# untitled.net
KiCad netlist of a schematic drawn in EAGLE
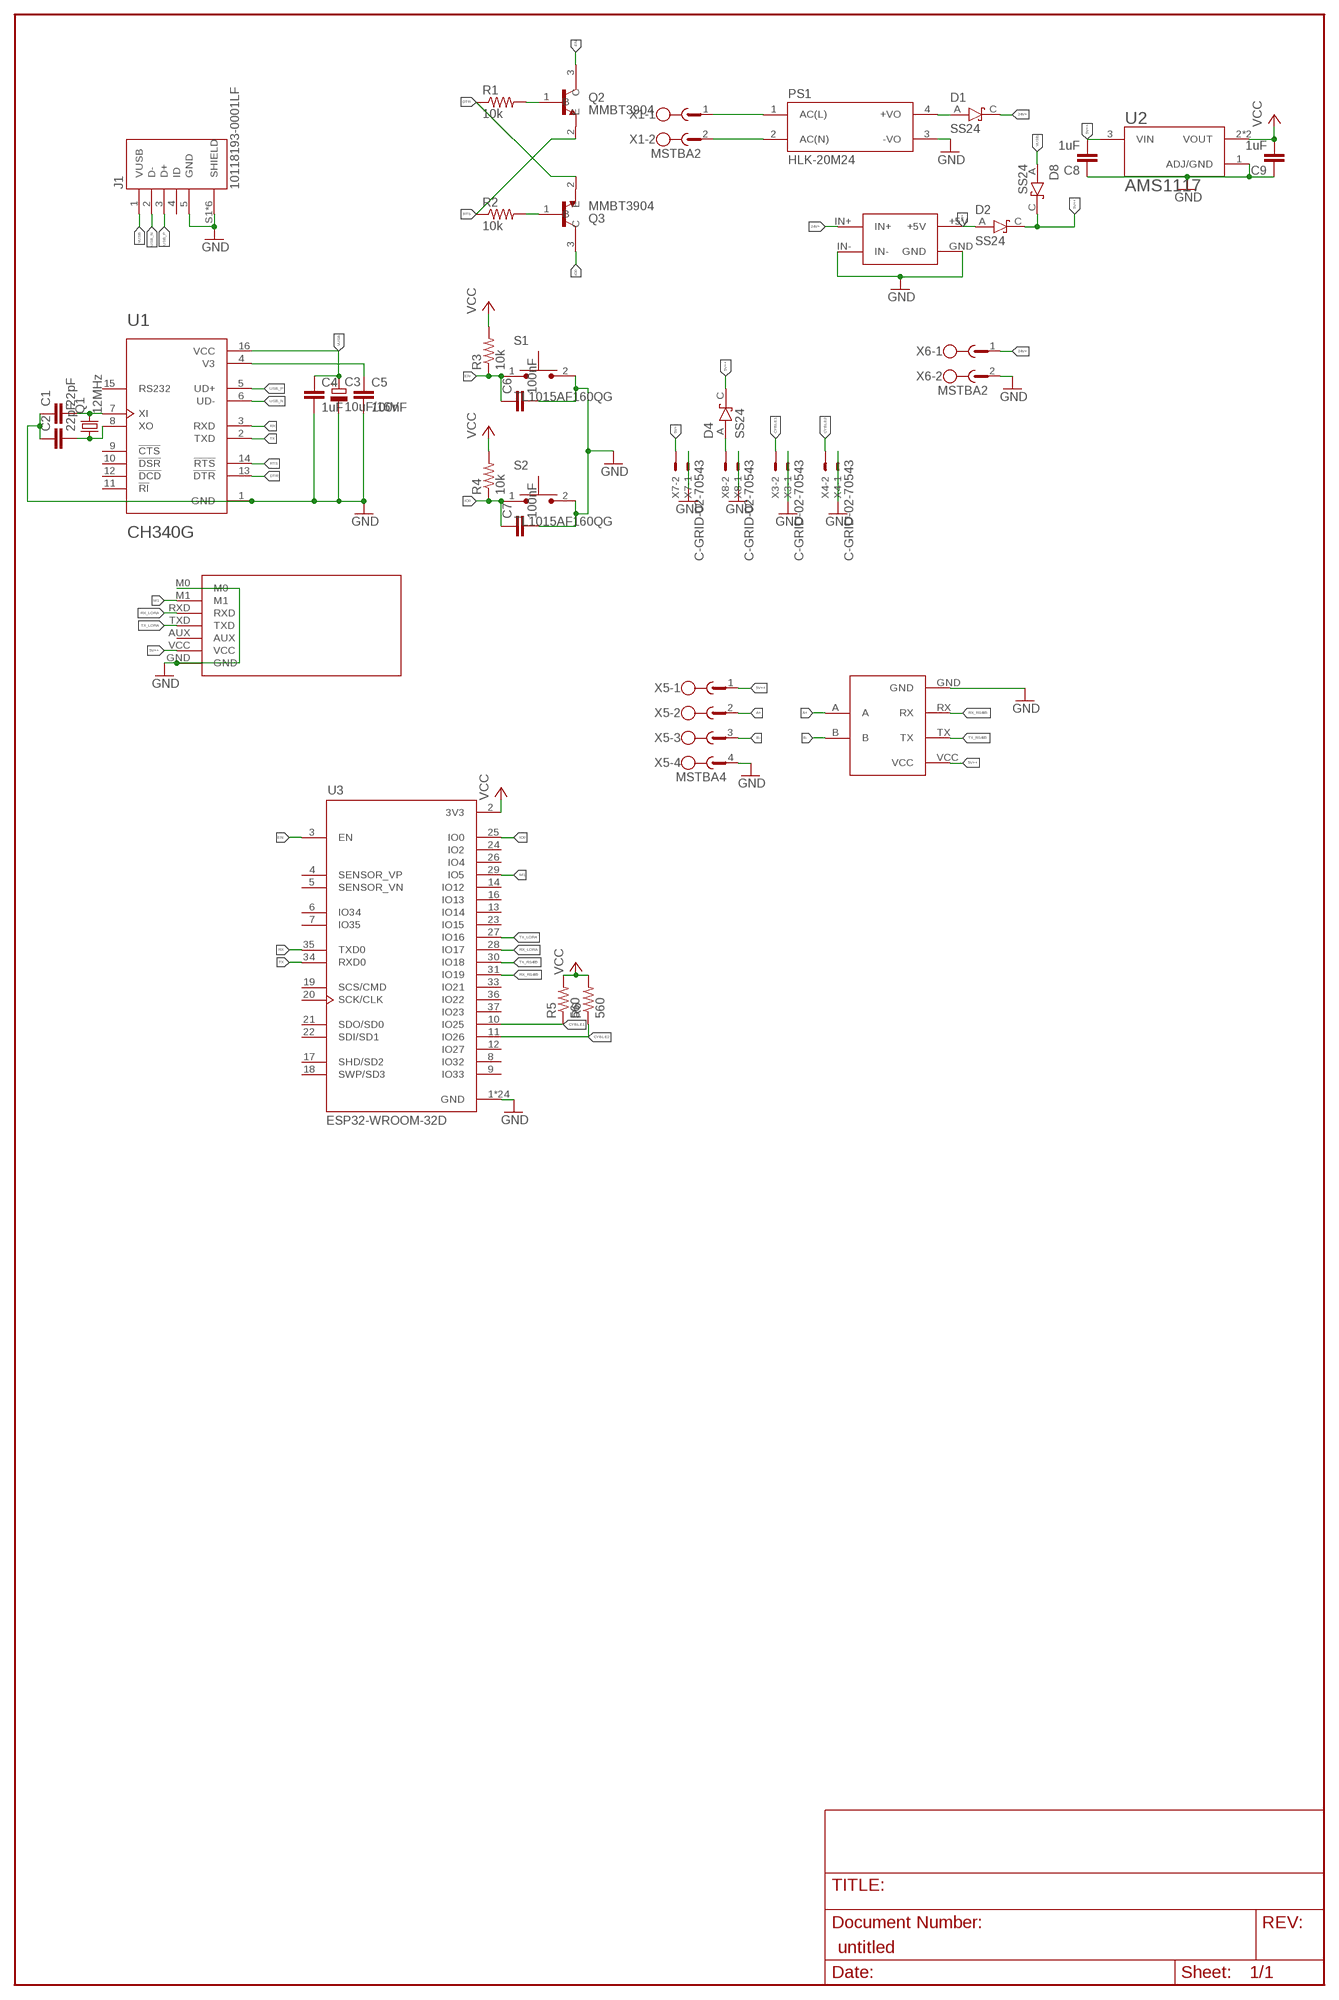
[diagram p0: schematic, sheet 1]

(export (version "E")
  (design (tool "Eeschema 10.0.6"))
  (components
    (comp (ref "C1")
      (value "22pF")
      (footprint "eagle-import:C0805K")
      (libsource (lib "eagle-import") (part "C-EUC0805K"))
    )
    (comp (ref "C2")
      (value "22pF")
      (footprint "eagle-import:C0805K")
      (libsource (lib "eagle-import") (part "C-EUC0805K"))
    )
    (comp (ref "C3")
      (value "10uF/16V")
      (footprint "eagle-import:153CLV-0505")
      (libsource (lib "eagle-import") (part "CPOL-EU153CLV-0505"))
    )
    (comp (ref "C4")
      (value "1uF")
      (footprint "eagle-import:C0805K")
      (libsource (lib "eagle-import") (part "C-EUC0805K"))
    )
    (comp (ref "C5")
      (value "100nF")
      (footprint "eagle-import:C0805K")
      (libsource (lib "eagle-import") (part "C-EUC0805K"))
    )
    (comp (ref "C6")
      (value "100nF")
      (footprint "eagle-import:C0805K")
      (libsource (lib "eagle-import") (part "C-EUC0805K"))
    )
    (comp (ref "C7")
      (value "100nF")
      (footprint "eagle-import:C0805K")
      (libsource (lib "eagle-import") (part "C-EUC0805K"))
    )
    (comp (ref "C8")
      (value "1uF")
      (footprint "eagle-import:C0805K")
      (libsource (lib "eagle-import") (part "C-EUC0805K"))
    )
    (comp (ref "C9")
      (value "1uF")
      (footprint "eagle-import:C0805K")
      (libsource (lib "eagle-import") (part "C-EUC0805K"))
    )
    (comp (ref "D1")
      (value "SS24")
      (footprint "eagle-import:DIOM5336X265N")
      (fields (field (name "MF") "ON Semiconductor"))
      (libsource (lib "eagle-import") (part "SS24"))
    )
    (comp (ref "D2")
      (value "SS24")
      (footprint "eagle-import:DIOM5336X265N")
      (fields (field (name "MF") "ON Semiconductor"))
      (libsource (lib "eagle-import") (part "SS24"))
    )
    (comp (ref "D4")
      (value "SS24")
      (footprint "eagle-import:DIOM5336X265N")
      (fields (field (name "MF") "ON Semiconductor"))
      (libsource (lib "eagle-import") (part "SS24"))
    )
    (comp (ref "D8")
      (value "SS24")
      (footprint "eagle-import:DIOM5336X265N")
      (fields (field (name "MF") "ON Semiconductor"))
      (libsource (lib "eagle-import") (part "SS24"))
    )
    (comp (ref "EBYTEE220-900T22D1")
      (value "EBYTEE220-900T22D")
      (footprint "eagle-import:EBYTEE220-900T22D")
      (libsource (lib "eagle-import") (part "EBYTEE220-900T22D"))
    )
    (comp (ref "J1")
      (value "10118193-0001LF")
      (footprint "eagle-import:FCI_10118193-0001LF")
      (fields (field (name "MF") "FCI"))
      (libsource (lib "eagle-import") (part "10118193-0001LF"))
    )
    (comp (ref "PS1")
      (value "HLK-20M24")
      (footprint "eagle-import:CONV_HLK-20M24")
      (fields (field (name "MF") "Hi-link"))
      (libsource (lib "eagle-import") (part "HLK-20M24"))
    )
    (comp (ref "Q1")
      (value "12MHz")
      (footprint "eagle-import:SM49")
      (libsource (lib "eagle-import") (part "CRYSTALSM49"))
    )
    (comp (ref "Q2")
      (value "MMBT3904")
      (footprint "eagle-import:SOT95P240X120-3N")
      (fields (field (name "MF") "ON Semiconductor"))
      (libsource (lib "eagle-import") (part "MMBT3904"))
    )
    (comp (ref "Q3")
      (value "MMBT3904")
      (footprint "eagle-import:SOT95P240X120-3N")
      (fields (field (name "MF") "ON Semiconductor"))
      (libsource (lib "eagle-import") (part "MMBT3904"))
    )
    (comp (ref "R1")
      (value "10k")
      (footprint "eagle-import:M0805")
      (libsource (lib "eagle-import") (part "R-US_M0805"))
    )
    (comp (ref "R2")
      (value "10k")
      (footprint "eagle-import:M0805")
      (libsource (lib "eagle-import") (part "R-US_M0805"))
    )
    (comp (ref "R3")
      (value "10k")
      (footprint "eagle-import:M0805")
      (libsource (lib "eagle-import") (part "R-US_M0805"))
    )
    (comp (ref "R4")
      (value "10k")
      (footprint "eagle-import:M0805")
      (libsource (lib "eagle-import") (part "R-US_M0805"))
    )
    (comp (ref "R5")
      (value "560")
      (footprint "eagle-import:M0805")
      (libsource (lib "eagle-import") (part "R-US_M0805"))
    )
    (comp (ref "R6")
      (value "560")
      (footprint "eagle-import:M0805")
      (libsource (lib "eagle-import") (part "R-US_M0805"))
    )
    (comp (ref "S1")
      (value "TL1015AF160QG")
      (footprint "eagle-import:SW_TL1015AF160QG")
      (fields (field (name "MF") "E-Switch"))
      (libsource (lib "eagle-import") (part "TL1015AF160QG"))
    )
    (comp (ref "S2")
      (value "TL1015AF160QG")
      (footprint "eagle-import:SW_TL1015AF160QG")
      (fields (field (name "MF") "E-Switch"))
      (libsource (lib "eagle-import") (part "TL1015AF160QG"))
    )
    (comp (ref "SUPER-STEPDOWN1")
      (value "SUPER-STEPDOWN")
      (footprint "eagle-import:SUPER-STEPDOWN")
      (libsource (lib "eagle-import") (part "SUPER-STEPDOWN"))
    )
    (comp (ref "TTL-RS1")
      (value "TTL-RS485")
      (footprint "eagle-import:TTL-RS485")
      (libsource (lib "eagle-import") (part "TTL-RS485"))
    )
    (comp (ref "U1")
      (value "CH340G")
      (footprint "eagle-import:SOIC127P600X180-16N")
      (fields (field (name "MF") "WCH") (field (name "MP") "Ch340G"))
      (libsource (lib "eagle-import") (part "CH340G"))
    )
    (comp (ref "U2")
      (value "AMS1117")
      (footprint "eagle-import:SOT229P700X180-4N")
      (fields (field (name "MF") "Advanced Monolithic Systems"))
      (libsource (lib "eagle-import") (part "AMS1117"))
    )
    (comp (ref "U3")
      (value "ESP32-WROOM-32D")
      (footprint "eagle-import:MODULE_ESP32-WROOM-32D")
      (fields (field (name "MF") "Espressif Systems"))
      (libsource (lib "eagle-import") (part "ESP32-WROOM-32D"))
    )
    (comp (ref "X1")
      (value "MSTBA2")
      (footprint "eagle-import:MSTBA2")
      (fields (field (name "MF") "FARNELL") (field (name "MPN") "1757242"))
      (libsource (lib "eagle-import") (part "MSTBA2"))
    )
    (comp (ref "X3")
      (value "C-GRID-02-70543")
      (footprint "eagle-import:70543-02")
      (fields (field (name "MF") "MOLEX"))
      (libsource (lib "eagle-import") (part "C-GRID-02-70543"))
    )
    (comp (ref "X4")
      (value "C-GRID-02-70543")
      (footprint "eagle-import:70543-02")
      (fields (field (name "MF") "MOLEX"))
      (libsource (lib "eagle-import") (part "C-GRID-02-70543"))
    )
    (comp (ref "X5")
      (value "MSTBA4")
      (footprint "eagle-import:MSTBA4")
      (fields (field (name "MF") "FARNELL") (field (name "MPN") "1757268"))
      (libsource (lib "eagle-import") (part "MSTBA4"))
    )
    (comp (ref "X6")
      (value "MSTBA2")
      (footprint "eagle-import:MSTBA2")
      (fields (field (name "MF") "FARNELL") (field (name "MPN") "1757242"))
      (libsource (lib "eagle-import") (part "MSTBA2"))
    )
    (comp (ref "X7")
      (value "C-GRID-02-70543")
      (footprint "eagle-import:70543-02")
      (fields (field (name "MF") "MOLEX"))
      (libsource (lib "eagle-import") (part "C-GRID-02-70543"))
    )
    (comp (ref "X8")
      (value "C-GRID-02-70543")
      (footprint "eagle-import:70543-02")
      (fields (field (name "MF") "MOLEX"))
      (libsource (lib "eagle-import") (part "C-GRID-02-70543"))
    )
  )
  (nets
    (net (code "1") (name "5V+") (class "Default")
      (node (ref "D2") (pin "A") (pinfunction "A_A") (pintype "passive"))
      (node (ref "SUPER-STEPDOWN1") (pin "+5V") (pinfunction "+5V_+5V") (pintype "bidirectional"))
      (node (ref "X7") (pin "2") (pinfunction "S_2") (pintype "passive"))
    )
    (net (code "2") (name "5V++") (class "Default")
      (node (ref "C8") (pin "2") (pinfunction "2_2") (pintype "passive"))
      (node (ref "D2") (pin "C") (pinfunction "K_C") (pintype "passive"))
      (node (ref "D4") (pin "C") (pinfunction "K_C") (pintype "passive"))
      (node (ref "D8") (pin "C") (pinfunction "K_C") (pintype "passive"))
      (node (ref "EBYTEE220-900T22D1") (pin "VCC") (pinfunction "VCC_VCC") (pintype "bidirectional"))
      (node (ref "TTL-RS1") (pin "VCC") (pinfunction "VCC_VCC") (pintype "bidirectional"))
      (node (ref "U2") (pin "3") (pinfunction "VIN_3") (pintype "input"))
      (node (ref "X5") (pin "1") (pinfunction "1_1") (pintype "passive"))
    )
    (net (code "3") (name "24V+") (class "Default")
      (node (ref "D1") (pin "C") (pinfunction "K_C") (pintype "passive"))
      (node (ref "SUPER-STEPDOWN1") (pin "IN+") (pinfunction "IN+_IN+") (pintype "bidirectional"))
      (node (ref "X6") (pin "1") (pinfunction "1_1") (pintype "passive"))
    )
    (net (code "4") (name "A+") (class "Default")
      (node (ref "TTL-RS1") (pin "A") (pinfunction "A_A") (pintype "bidirectional"))
      (node (ref "X5") (pin "2") (pinfunction "1_2") (pintype "passive"))
    )
    (net (code "5") (name "B-") (class "Default")
      (node (ref "TTL-RS1") (pin "B") (pinfunction "B_B") (pintype "bidirectional"))
      (node (ref "X5") (pin "3") (pinfunction "1_3") (pintype "passive"))
    )
    (net (code "6") (name "CYBLE1") (class "Default")
      (node (ref "R5") (pin "1") (pinfunction "1_1") (pintype "passive"))
      (node (ref "U3") (pin "10") (pinfunction "IO25_10") (pintype "bidirectional"))
      (node (ref "X3") (pin "2") (pinfunction "S_2") (pintype "passive"))
    )
    (net (code "7") (name "CYBLE2") (class "Default")
      (node (ref "R6") (pin "1") (pinfunction "1_1") (pintype "passive"))
      (node (ref "U3") (pin "11") (pinfunction "IO26_11") (pintype "bidirectional"))
      (node (ref "X4") (pin "2") (pinfunction "S_2") (pintype "passive"))
    )
    (net (code "8") (name "DTR") (class "Default")
      (node (ref "Q3") (pin "2") (pinfunction "E_2") (pintype "passive"))
      (node (ref "R1") (pin "1") (pinfunction "1_1") (pintype "passive"))
      (node (ref "U1") (pin "13") (pinfunction "~{DTR}_13") (pintype "output"))
    )
    (net (code "9") (name "EN") (class "Default")
      (node (ref "C6") (pin "1") (pinfunction "1_1") (pintype "passive"))
      (node (ref "Q2") (pin "3") (pinfunction "C_3") (pintype "passive"))
      (node (ref "R3") (pin "1") (pinfunction "1_1") (pintype "passive"))
      (node (ref "S1") (pin "1") (pinfunction "1_1") (pintype "passive"))
      (node (ref "U3") (pin "3") (pinfunction "EN_3") (pintype "input"))
    )
    (net (code "10") (name "GND") (class "Default")
      (node (ref "C1") (pin "1") (pinfunction "1_1") (pintype "passive"))
      (node (ref "C2") (pin "1") (pinfunction "1_1") (pintype "passive"))
      (node (ref "C3") (pin "-") (pinfunction "-_-") (pintype "passive"))
      (node (ref "C4") (pin "2") (pinfunction "2_2") (pintype "passive"))
      (node (ref "C5") (pin "2") (pinfunction "2_2") (pintype "passive"))
      (node (ref "C6") (pin "2") (pinfunction "2_2") (pintype "passive"))
      (node (ref "C7") (pin "2") (pinfunction "2_2") (pintype "passive"))
      (node (ref "C8") (pin "1") (pinfunction "1_1") (pintype "passive"))
      (node (ref "C9") (pin "1") (pinfunction "1_1") (pintype "passive"))
      (node (ref "EBYTEE220-900T22D1") (pin "GND") (pinfunction "GND_GND") (pintype "bidirectional"))
      (node (ref "EBYTEE220-900T22D1") (pin "M0") (pinfunction "M0_M0") (pintype "bidirectional"))
      (node (ref "J1") (pin "5") (pinfunction "GND_5") (pintype "passive"))
      (node (ref "J1") (pin "S1") (pinfunction "SHIELD_S1") (pintype "passive"))
      (node (ref "J1") (pin "S2") (pinfunction "SHIELD_S2") (pintype "passive"))
      (node (ref "J1") (pin "S3") (pinfunction "SHIELD_S3") (pintype "passive"))
      (node (ref "J1") (pin "S4") (pinfunction "SHIELD_S4") (pintype "passive"))
      (node (ref "J1") (pin "S5") (pinfunction "SHIELD_S5") (pintype "passive"))
      (node (ref "J1") (pin "S6") (pinfunction "SHIELD_S6") (pintype "passive"))
      (node (ref "PS1") (pin "3") (pinfunction "-VO_3") (pintype "output"))
      (node (ref "S1") (pin "2") (pinfunction "2_2") (pintype "passive"))
      (node (ref "S2") (pin "2") (pinfunction "2_2") (pintype "passive"))
      (node (ref "SUPER-STEPDOWN1") (pin "GND") (pinfunction "GND_GND") (pintype "bidirectional"))
      (node (ref "SUPER-STEPDOWN1") (pin "IN-") (pinfunction "IN-_IN-") (pintype "bidirectional"))
      (node (ref "TTL-RS1") (pin "GND") (pinfunction "GND_GND") (pintype "bidirectional"))
      (node (ref "U1") (pin "1") (pinfunction "GND_1") (pintype "power_in"))
      (node (ref "U2") (pin "1") (pinfunction "ADJ/GND_1") (pintype "power_in"))
      (node (ref "U3") (pin "1") (pinfunction "GND_1") (pintype "power_in"))
      (node (ref "U3") (pin "15") (pinfunction "GND_15") (pintype "power_in"))
      (node (ref "U3") (pin "38") (pinfunction "GND_38") (pintype "power_in"))
      (node (ref "U3") (pin "39_1") (pinfunction "GND_39_1") (pintype "power_in"))
      (node (ref "U3") (pin "39_10") (pinfunction "GND_39_10") (pintype "power_in"))
      (node (ref "U3") (pin "39_11") (pinfunction "GND_39_11") (pintype "power_in"))
      (node (ref "U3") (pin "39_12") (pinfunction "GND_39_12") (pintype "power_in"))
      (node (ref "U3") (pin "39_13") (pinfunction "GND_39_13") (pintype "power_in"))
      (node (ref "U3") (pin "39_14") (pinfunction "GND_39_14") (pintype "power_in"))
      (node (ref "U3") (pin "39_15") (pinfunction "GND_39_15") (pintype "power_in"))
      (node (ref "U3") (pin "39_16") (pinfunction "GND_39_16") (pintype "power_in"))
      (node (ref "U3") (pin "39_17") (pinfunction "GND_39_17") (pintype "power_in"))
      (node (ref "U3") (pin "39_18") (pinfunction "GND_39_18") (pintype "power_in"))
      (node (ref "U3") (pin "39_19") (pinfunction "GND_39_19") (pintype "power_in"))
      (node (ref "U3") (pin "39_2") (pinfunction "GND_39_2") (pintype "power_in"))
      (node (ref "U3") (pin "39_20") (pinfunction "GND_39_20") (pintype "power_in"))
      (node (ref "U3") (pin "39_21") (pinfunction "GND_39_21") (pintype "power_in"))
      (node (ref "U3") (pin "39_3") (pinfunction "GND_39_3") (pintype "power_in"))
      (node (ref "U3") (pin "39_4") (pinfunction "GND_39_4") (pintype "power_in"))
      (node (ref "U3") (pin "39_5") (pinfunction "GND_39_5") (pintype "power_in"))
      (node (ref "U3") (pin "39_6") (pinfunction "GND_39_6") (pintype "power_in"))
      (node (ref "U3") (pin "39_7") (pinfunction "GND_39_7") (pintype "power_in"))
      (node (ref "U3") (pin "39_8") (pinfunction "GND_39_8") (pintype "power_in"))
      (node (ref "U3") (pin "39_9") (pinfunction "GND_39_9") (pintype "power_in"))
      (node (ref "X3") (pin "1") (pinfunction "S_1") (pintype "passive"))
      (node (ref "X4") (pin "1") (pinfunction "S_1") (pintype "passive"))
      (node (ref "X5") (pin "4") (pinfunction "1_4") (pintype "passive"))
      (node (ref "X6") (pin "2") (pinfunction "1_2") (pintype "passive"))
      (node (ref "X7") (pin "1") (pinfunction "S_1") (pintype "passive"))
      (node (ref "X8") (pin "1") (pinfunction "S_1") (pintype "passive"))
    )
    (net (code "11") (name "IO0") (class "Default")
      (node (ref "C7") (pin "1") (pinfunction "1_1") (pintype "passive"))
      (node (ref "Q3") (pin "3") (pinfunction "C_3") (pintype "passive"))
      (node (ref "R4") (pin "1") (pinfunction "1_1") (pintype "passive"))
      (node (ref "S2") (pin "1") (pinfunction "1_1") (pintype "passive"))
      (node (ref "U3") (pin "25") (pinfunction "IO0_25") (pintype "bidirectional"))
    )
    (net (code "12") (name "M1") (class "Default")
      (node (ref "EBYTEE220-900T22D1") (pin "M1") (pinfunction "M1_M1") (pintype "bidirectional"))
      (node (ref "U3") (pin "29") (pinfunction "IO5_29") (pintype "bidirectional"))
    )
    (net (code "13") (name "Net-(PS1-+VO)") (class "Default")
      (node (ref "D1") (pin "A") (pinfunction "A_A") (pintype "passive"))
      (node (ref "PS1") (pin "4") (pinfunction "+VO_4") (pintype "output"))
    )
    (net (code "14") (name "Net-(PS1-AC(L))") (class "Default")
      (node (ref "PS1") (pin "1") (pinfunction "AC(L)_1") (pintype "input"))
      (node (ref "X1") (pin "1") (pinfunction "1_1") (pintype "passive"))
    )
    (net (code "15") (name "Net-(PS1-AC(N))") (class "Default")
      (node (ref "PS1") (pin "2") (pinfunction "AC(N)_2") (pintype "input"))
      (node (ref "X1") (pin "2") (pinfunction "1_2") (pintype "passive"))
    )
    (net (code "16") (name "Net-(Q2-B)") (class "Default")
      (node (ref "Q2") (pin "1") (pinfunction "B_1") (pintype "passive"))
      (node (ref "R1") (pin "2") (pinfunction "2_2") (pintype "passive"))
    )
    (net (code "17") (name "Net-(Q3-B)") (class "Default")
      (node (ref "Q3") (pin "1") (pinfunction "B_1") (pintype "passive"))
      (node (ref "R2") (pin "2") (pinfunction "2_2") (pintype "passive"))
    )
    (net (code "18") (name "Net-(U1-V3)") (class "Default")
      (node (ref "C5") (pin "1") (pinfunction "1_1") (pintype "passive"))
      (node (ref "U1") (pin "4") (pinfunction "V3_4") (pintype "power_in"))
    )
    (net (code "19") (name "Net-(U1-XI)") (class "Default")
      (node (ref "C1") (pin "2") (pinfunction "2_2") (pintype "passive"))
      (node (ref "Q1") (pin "2") (pinfunction "2_2") (pintype "passive"))
      (node (ref "U1") (pin "7") (pinfunction "XI_7") (pintype "input"))
    )
    (net (code "20") (name "Net-(U1-XO)") (class "Default")
      (node (ref "C2") (pin "2") (pinfunction "2_2") (pintype "passive"))
      (node (ref "Q1") (pin "1") (pinfunction "1_1") (pintype "passive"))
      (node (ref "U1") (pin "8") (pinfunction "XO_8") (pintype "output"))
    )
    (net (code "21") (name "Net-(X8B-S)") (class "Default")
      (node (ref "D4") (pin "A") (pinfunction "A_A") (pintype "passive"))
      (node (ref "X8") (pin "2") (pinfunction "S_2") (pintype "passive"))
    )
    (net (code "22") (name "RTS") (class "Default")
      (node (ref "Q2") (pin "2") (pinfunction "E_2") (pintype "passive"))
      (node (ref "R2") (pin "1") (pinfunction "1_1") (pintype "passive"))
      (node (ref "U1") (pin "14") (pinfunction "~{RTS}_14") (pintype "output"))
    )
    (net (code "23") (name "RX") (class "Default")
      (node (ref "U1") (pin "3") (pinfunction "RXD_3") (pintype "input"))
      (node (ref "U3") (pin "35") (pinfunction "TXD0_35") (pintype "bidirectional"))
    )
    (net (code "24") (name "RX_LORA") (class "Default")
      (node (ref "EBYTEE220-900T22D1") (pin "RXD") (pinfunction "RXD_RXD") (pintype "bidirectional"))
      (node (ref "U3") (pin "28") (pinfunction "IO17_28") (pintype "bidirectional"))
    )
    (net (code "25") (name "RX_RS485") (class "Default")
      (node (ref "TTL-RS1") (pin "RX") (pinfunction "RX_RX") (pintype "bidirectional"))
      (node (ref "U3") (pin "31") (pinfunction "IO19_31") (pintype "bidirectional"))
    )
    (net (code "26") (name "TX") (class "Default")
      (node (ref "U1") (pin "2") (pinfunction "TXD_2") (pintype "output"))
      (node (ref "U3") (pin "34") (pinfunction "RXD0_34") (pintype "bidirectional"))
    )
    (net (code "27") (name "TX_LORA") (class "Default")
      (node (ref "EBYTEE220-900T22D1") (pin "TXD") (pinfunction "TXD_TXD") (pintype "bidirectional"))
      (node (ref "U3") (pin "27") (pinfunction "IO16_27") (pintype "bidirectional"))
    )
    (net (code "28") (name "TX_RS485") (class "Default")
      (node (ref "TTL-RS1") (pin "TX") (pinfunction "TX_TX") (pintype "bidirectional"))
      (node (ref "U3") (pin "30") (pinfunction "IO18_30") (pintype "bidirectional"))
    )
    (net (code "29") (name "USB_N") (class "Default")
      (node (ref "J1") (pin "2") (pinfunction "D-_2") (pintype "passive"))
      (node (ref "U1") (pin "6") (pinfunction "UD-_6") (pintype "bidirectional"))
    )
    (net (code "30") (name "USB_P") (class "Default")
      (node (ref "J1") (pin "3") (pinfunction "D+_3") (pintype "passive"))
      (node (ref "U1") (pin "5") (pinfunction "UD+_5") (pintype "bidirectional"))
    )
    (net (code "31") (name "VCC") (class "Default")
      (node (ref "C9") (pin "2") (pinfunction "2_2") (pintype "passive"))
      (node (ref "R3") (pin "2") (pinfunction "2_2") (pintype "passive"))
      (node (ref "R4") (pin "2") (pinfunction "2_2") (pintype "passive"))
      (node (ref "R5") (pin "2") (pinfunction "2_2") (pintype "passive"))
      (node (ref "R6") (pin "2") (pinfunction "2_2") (pintype "passive"))
      (node (ref "U2") (pin "2") (pinfunction "VOUT_2") (pintype "output"))
      (node (ref "U2") (pin "4") (pinfunction "VOUT_4") (pintype "output"))
      (node (ref "U3") (pin "2") (pinfunction "3V3_2") (pintype "power_in"))
    )
    (net (code "32") (name "VUSB") (class "Default")
      (node (ref "C3") (pin "+") (pinfunction "+_+") (pintype "passive"))
      (node (ref "C4") (pin "1") (pinfunction "1_1") (pintype "passive"))
      (node (ref "D8") (pin "A") (pinfunction "A_A") (pintype "passive"))
      (node (ref "J1") (pin "1") (pinfunction "VUSB_1") (pintype "passive"))
      (node (ref "U1") (pin "16") (pinfunction "VCC_16") (pintype "power_in"))
    )
    (net (code "33") (name "unconnected-(EBYTEE220-900T22D1-PadAUX)") (class "Default")
      (node (ref "EBYTEE220-900T22D1") (pin "AUX") (pinfunction "AUX_AUX") (pintype "bidirectional"))
    )
    (net (code "34") (name "unconnected-(J1-ID-Pad4)") (class "Default")
      (node (ref "J1") (pin "4") (pinfunction "ID_4") (pintype "passive"))
    )
    (net (code "35") (name "unconnected-(U1-RS232-Pad15)") (class "Default")
      (node (ref "U1") (pin "15") (pinfunction "RS232_15") (pintype "input"))
    )
    (net (code "36") (name "unconnected-(U1-~{CTS}-Pad9)") (class "Default")
      (node (ref "U1") (pin "9") (pinfunction "~{CTS}_9") (pintype "input"))
    )
    (net (code "37") (name "unconnected-(U1-~{DCD}-Pad12)") (class "Default")
      (node (ref "U1") (pin "12") (pinfunction "~{DCD}_12") (pintype "input"))
    )
    (net (code "38") (name "unconnected-(U1-~{DSR}-Pad10)") (class "Default")
      (node (ref "U1") (pin "10") (pinfunction "~{DSR}_10") (pintype "input"))
    )
    (net (code "39") (name "unconnected-(U1-~{RI}-Pad11)") (class "Default")
      (node (ref "U1") (pin "11") (pinfunction "~{RI}_11") (pintype "input"))
    )
    (net (code "40") (name "unconnected-(U3-IO2-Pad24)") (class "Default")
      (node (ref "U3") (pin "24") (pinfunction "IO2_24") (pintype "bidirectional"))
    )
    (net (code "41") (name "unconnected-(U3-IO4-Pad26)") (class "Default")
      (node (ref "U3") (pin "26") (pinfunction "IO4_26") (pintype "bidirectional"))
    )
    (net (code "42") (name "unconnected-(U3-IO12-Pad14)") (class "Default")
      (node (ref "U3") (pin "14") (pinfunction "IO12_14") (pintype "bidirectional"))
    )
    (net (code "43") (name "unconnected-(U3-IO13-Pad16)") (class "Default")
      (node (ref "U3") (pin "16") (pinfunction "IO13_16") (pintype "bidirectional"))
    )
    (net (code "44") (name "unconnected-(U3-IO14-Pad13)") (class "Default")
      (node (ref "U3") (pin "13") (pinfunction "IO14_13") (pintype "bidirectional"))
    )
    (net (code "45") (name "unconnected-(U3-IO15-Pad23)") (class "Default")
      (node (ref "U3") (pin "23") (pinfunction "IO15_23") (pintype "bidirectional"))
    )
    (net (code "46") (name "unconnected-(U3-IO21-Pad33)") (class "Default")
      (node (ref "U3") (pin "33") (pinfunction "IO21_33") (pintype "bidirectional"))
    )
    (net (code "47") (name "unconnected-(U3-IO22-Pad36)") (class "Default")
      (node (ref "U3") (pin "36") (pinfunction "IO22_36") (pintype "bidirectional"))
    )
    (net (code "48") (name "unconnected-(U3-IO23-Pad37)") (class "Default")
      (node (ref "U3") (pin "37") (pinfunction "IO23_37") (pintype "bidirectional"))
    )
    (net (code "49") (name "unconnected-(U3-IO27-Pad12)") (class "Default")
      (node (ref "U3") (pin "12") (pinfunction "IO27_12") (pintype "bidirectional"))
    )
    (net (code "50") (name "unconnected-(U3-IO32-Pad8)") (class "Default")
      (node (ref "U3") (pin "8") (pinfunction "IO32_8") (pintype "bidirectional"))
    )
    (net (code "51") (name "unconnected-(U3-IO33-Pad9)") (class "Default")
      (node (ref "U3") (pin "9") (pinfunction "IO33_9") (pintype "bidirectional"))
    )
    (net (code "52") (name "unconnected-(U3-IO34-Pad6)") (class "Default")
      (node (ref "U3") (pin "6") (pinfunction "IO34_6") (pintype "input"))
    )
    (net (code "53") (name "unconnected-(U3-IO35-Pad7)") (class "Default")
      (node (ref "U3") (pin "7") (pinfunction "IO35_7") (pintype "input"))
    )
    (net (code "54") (name "unconnected-(U3-SCK{slash}CLK-Pad20)") (class "Default")
      (node (ref "U3") (pin "20") (pinfunction "SCK/CLK_20") (pintype "bidirectional"))
    )
    (net (code "55") (name "unconnected-(U3-SCS{slash}CMD-Pad19)") (class "Default")
      (node (ref "U3") (pin "19") (pinfunction "SCS/CMD_19") (pintype "bidirectional"))
    )
    (net (code "56") (name "unconnected-(U3-SDI{slash}SD1-Pad22)") (class "Default")
      (node (ref "U3") (pin "22") (pinfunction "SDI/SD1_22") (pintype "bidirectional"))
    )
    (net (code "57") (name "unconnected-(U3-SDO{slash}SD0-Pad21)") (class "Default")
      (node (ref "U3") (pin "21") (pinfunction "SDO/SD0_21") (pintype "bidirectional"))
    )
    (net (code "58") (name "unconnected-(U3-SENSOR_VN-Pad5)") (class "Default")
      (node (ref "U3") (pin "5") (pinfunction "SENSOR_VN_5") (pintype "input"))
    )
    (net (code "59") (name "unconnected-(U3-SENSOR_VP-Pad4)") (class "Default")
      (node (ref "U3") (pin "4") (pinfunction "SENSOR_VP_4") (pintype "input"))
    )
    (net (code "60") (name "unconnected-(U3-SHD{slash}SD2-Pad17)") (class "Default")
      (node (ref "U3") (pin "17") (pinfunction "SHD/SD2_17") (pintype "bidirectional"))
    )
    (net (code "61") (name "unconnected-(U3-SWP{slash}SD3-Pad18)") (class "Default")
      (node (ref "U3") (pin "18") (pinfunction "SWP/SD3_18") (pintype "bidirectional"))
    )
  )
)
